# RevolvingStageController.net
KiCad netlist of a schematic drawn in Altium Designer
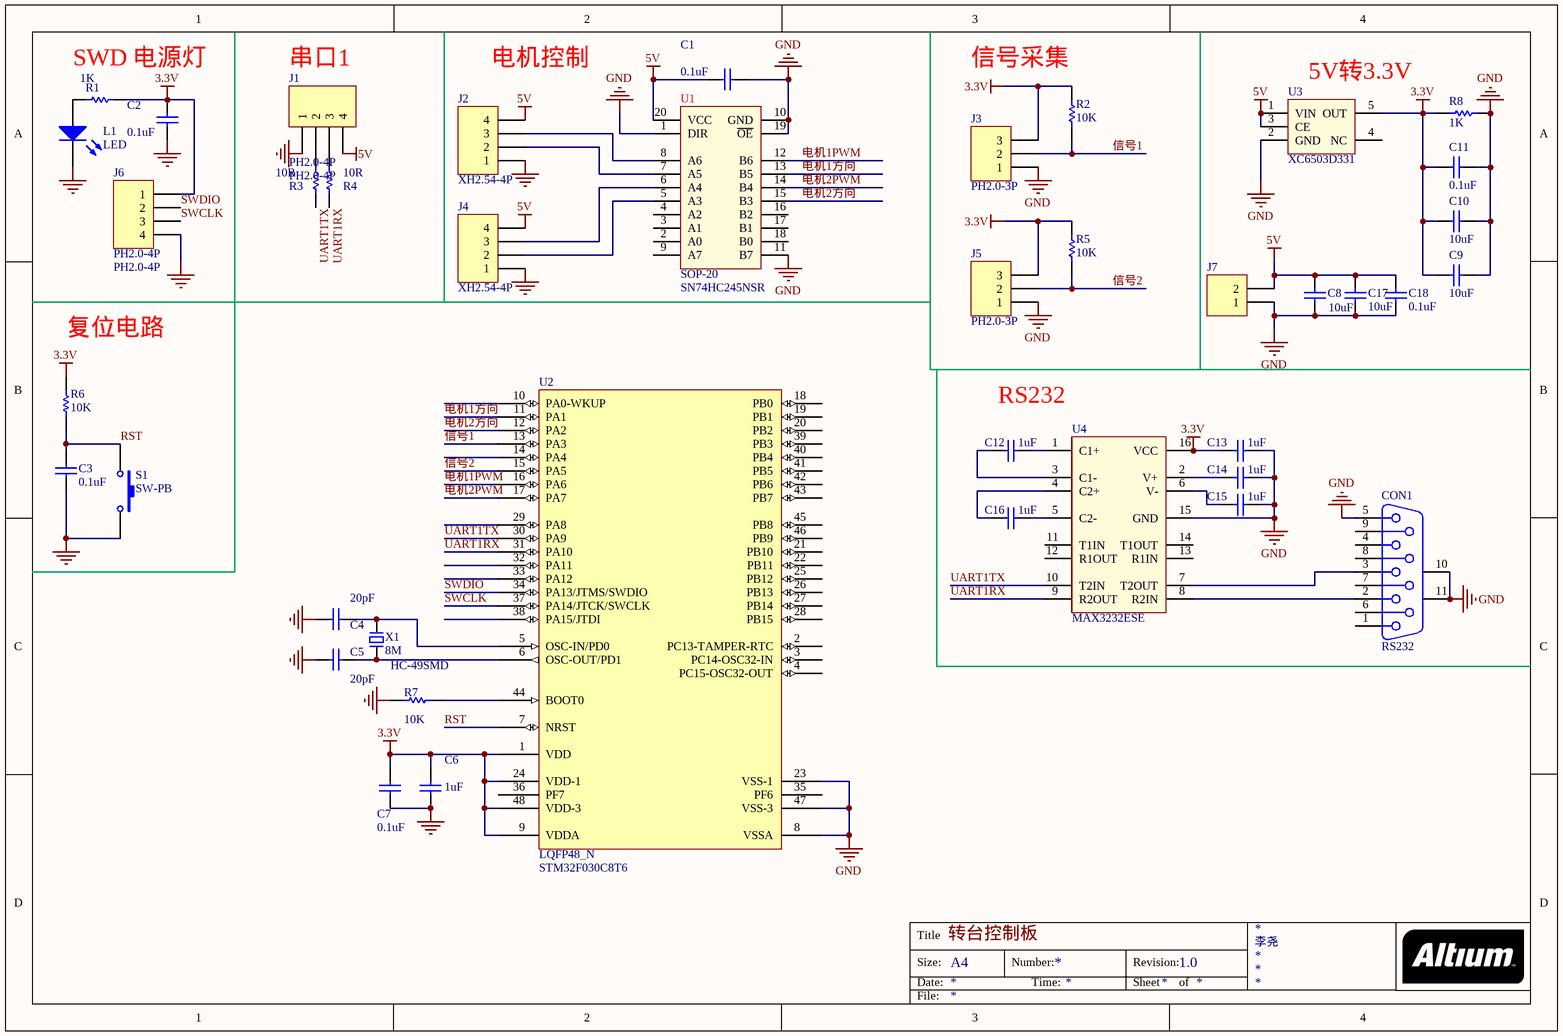
[diagram p0: RevolvingStageController.SchDoc]

(export (version "E")
  (design (tool "Eeschema 10.0.6"))
  (components
    (comp (ref "C1")
      (value "0.1uF")
      (footprint "0603")
      (description "Capacitor")
      (fields (field (name "PUBLISHER") "Altium Limited"))
      (libsource (lib "Miscellaneous Devices") (part "Cap"))
    )
    (comp (ref "C2")
      (value "0.1uF")
      (footprint "0603")
      (description "Capacitor")
      (fields (field (name "PUBLISHER") "Altium Limited"))
      (libsource (lib "Miscellaneous Devices") (part "Cap"))
    )
    (comp (ref "C3")
      (value "0.1uF")
      (footprint "0603")
      (description "Capacitor")
      (fields (field (name "PUBLISHER") "Altium Limited"))
      (libsource (lib "Miscellaneous Devices") (part "Cap"))
    )
    (comp (ref "C4")
      (value "20pF")
      (footprint "0603")
      (description "Capacitor")
      (fields (field (name "PUBLISHER") "Altium Limited"))
      (libsource (lib "Miscellaneous Devices") (part "Cap"))
    )
    (comp (ref "C5")
      (value "20pF")
      (footprint "0603")
      (description "Capacitor")
      (fields (field (name "PUBLISHER") "Altium Limited"))
      (libsource (lib "Miscellaneous Devices") (part "Cap"))
    )
    (comp (ref "C6")
      (value "1uF")
      (footprint "0603")
      (description "Capacitor")
      (fields (field (name "PUBLISHER") "Altium Limited"))
      (libsource (lib "Miscellaneous Devices") (part "Cap"))
    )
    (comp (ref "C7")
      (value "0.1uF")
      (footprint "0603")
      (description "Capacitor")
      (fields (field (name "PUBLISHER") "Altium Limited"))
      (libsource (lib "Miscellaneous Devices") (part "Cap"))
    )
    (comp (ref "C8")
      (value "10uF")
      (footprint "0603")
      (description "Capacitor")
      (fields (field (name "PUBLISHER") "Altium Limited"))
      (libsource (lib "Miscellaneous Devices") (part "Cap"))
    )
    (comp (ref "C9")
      (value "10uF")
      (footprint "0603")
      (description "Capacitor")
      (fields (field (name "PUBLISHER") "Altium Limited"))
      (libsource (lib "Miscellaneous Devices") (part "Cap"))
    )
    (comp (ref "C10")
      (value "10uF")
      (footprint "0603")
      (description "Capacitor")
      (fields (field (name "PUBLISHER") "Altium Limited"))
      (libsource (lib "Miscellaneous Devices") (part "Cap"))
    )
    (comp (ref "C11")
      (value "0.1uF")
      (footprint "0603")
      (description "Capacitor")
      (fields (field (name "PUBLISHER") "Altium Limited"))
      (libsource (lib "Miscellaneous Devices") (part "Cap"))
    )
    (comp (ref "C12")
      (value "1uF")
      (footprint "LiyaoPCB库:0603")
      (description "Capacitor")
      (fields (field (name "PUBLISHER") "Altium Limited"))
      (libsource (lib "Miscellaneous Devices") (part "Cap"))
    )
    (comp (ref "C13")
      (value "1uF")
      (footprint "0603")
      (description "Capacitor")
      (fields (field (name "PUBLISHER") "Altium Limited"))
      (libsource (lib "Miscellaneous Devices") (part "Cap"))
    )
    (comp (ref "C14")
      (value "1uF")
      (footprint "0603")
      (description "Capacitor")
      (fields (field (name "PUBLISHER") "Altium Limited"))
      (libsource (lib "Miscellaneous Devices") (part "Cap"))
    )
    (comp (ref "C15")
      (value "1uF")
      (footprint "0603")
      (description "Capacitor")
      (fields (field (name "PUBLISHER") "Altium Limited"))
      (libsource (lib "Miscellaneous Devices") (part "Cap"))
    )
    (comp (ref "C16")
      (value "1uF")
      (footprint "0603")
      (description "Capacitor")
      (fields (field (name "PUBLISHER") "Altium Limited"))
      (libsource (lib "Miscellaneous Devices") (part "Cap"))
    )
    (comp (ref "C17")
      (value "10uF")
      (footprint "0603")
      (description "电容0603")
      (fields (field (name "PUBLISHER") "Altium Limited"))
      (libsource (lib "Liyao原理图库") (part "Cap"))
    )
    (comp (ref "C18")
      (value "0.1uF")
      (footprint "0603")
      (description "电容0603")
      (fields (field (name "PUBLISHER") "Altium Limited"))
      (libsource (lib "Liyao原理图库") (part "Cap"))
    )
    (comp (ref "CON1")
      (value "RS232")
      (footprint "DSUB1.385-2H9-M")
      (description "Receptacle Assembly, 9 Position, Right Angle")
      (fields (field (name "PUBLISHER") "Altium Limited"))
      (libsource (lib "Liyao原理图库") (part "D Connector 9"))
    )
    (comp (ref "J1")
      (value "PH2.0-4P")
      (footprint "PH2.0-4P")
      (description "Header, 4-Pin")
      (fields (field (name "ALTIUM_VALUE") "PH2.0-4P") (field (name "PUBLISHER") "Altium Limited"))
      (libsource (lib "Miscellaneous Connectors") (part "Header 4"))
    )
    (comp (ref "J2")
      (value "XH2.54-4P")
      (footprint "XH2.54-4")
      (description "Header, 4-Pin")
      (fields (field (name "PUBLISHER") "Altium Limited"))
      (libsource (lib "") (part "Header 4_2"))
    )
    (comp (ref "J3")
      (value "PH2.0-3P")
      (footprint "PH2.0-3P")
      (description "Header, 3-Pin")
      (fields (field (name "PUBLISHER") "Altium Limited"))
      (libsource (lib "Sparks") (part "Header 3"))
    )
    (comp (ref "J4")
      (value "XH2.54-4P")
      (footprint "XH2.54-4")
      (description "Header, 4-Pin")
      (fields (field (name "PUBLISHER") "Altium Limited"))
      (libsource (lib "") (part "Header 4_2"))
    )
    (comp (ref "J5")
      (value "PH2.0-3P")
      (footprint "PH2.0-3P")
      (description "Header, 3-Pin")
      (fields (field (name "PUBLISHER") "Altium Limited"))
      (libsource (lib "Sparks") (part "Header 3"))
    )
    (comp (ref "J6")
      (value "PH2.0-4P")
      (footprint "PH2.0-4P")
      (description "Header, 4-Pin")
      (fields (field (name "ALTIUM_VALUE") "PH2.0-4P") (field (name "PUBLISHER") "Altium Limited"))
      (libsource (lib "") (part "Header 4_1"))
    )
    (comp (ref "J7")
      (value "PH2.0-2P")
      (footprint "PH2.0-2P")
      (description "插座PH2.0-2P")
      (fields (field (name "PUBLISHER") "Altium Limited"))
      (libsource (lib "Liyao原理图库") (part "PH2.0-2P"))
    )
    (comp (ref "L1") (value "LED") (footprint "0603") (libsource (lib "Sparks") (part "LED")))
    (comp (ref "R1")
      (value "1K")
      (footprint "0603")
      (description "Resistor")
      (fields (field (name "PUBLISHER") "Altium Limited"))
      (libsource (lib "Miscellaneous Devices") (part "Res1"))
    )
    (comp (ref "R2")
      (value "10K")
      (footprint "0603")
      (description "Resistor")
      (fields (field (name "PUBLISHER") "Altium Limited"))
      (libsource (lib "Miscellaneous Devices") (part "Res1"))
    )
    (comp (ref "R3")
      (value "10R")
      (footprint "0603")
      (description "Resistor")
      (fields (field (name "PUBLISHER") "Altium Limited"))
      (libsource (lib "Miscellaneous Devices") (part "Res1"))
    )
    (comp (ref "R4")
      (value "10R")
      (footprint "0603")
      (description "Resistor")
      (fields (field (name "PUBLISHER") "Altium Limited"))
      (libsource (lib "Miscellaneous Devices") (part "Res1"))
    )
    (comp (ref "R5")
      (value "10K")
      (footprint "0603")
      (description "Resistor")
      (fields (field (name "PUBLISHER") "Altium Limited"))
      (libsource (lib "Miscellaneous Devices") (part "Res1"))
    )
    (comp (ref "R6")
      (value "10K")
      (footprint "0603")
      (description "Resistor")
      (fields (field (name "PUBLISHER") "Altium Limited"))
      (libsource (lib "Miscellaneous Devices") (part "Res1"))
    )
    (comp (ref "R7")
      (value "10K")
      (footprint "0603")
      (description "Resistor")
      (fields (field (name "PUBLISHER") "Altium Limited"))
      (libsource (lib "Miscellaneous Devices") (part "Res1"))
    )
    (comp (ref "R8")
      (value "1K")
      (footprint "0603")
      (description "Resistor")
      (fields (field (name "PUBLISHER") "Altium Limited"))
      (libsource (lib "Miscellaneous Devices") (part "Res1"))
    )
    (comp (ref "S1")
      (value "SW-PB")
      (footprint "SW-KEY")
      (description "Switch")
      (fields (field (name "PUBLISHER") "Altium Limited"))
      (libsource (lib "Miscellaneous Devices") (part "SW-PB"))
    )
    (comp (ref "U1")
      (value "SOP-20")
      (footprint "SOP-20")
      (fields (field (name "ALTIUM_VALUE") "SN74HC245NSR"))
      (libsource (lib "SCH") (part "74HC245"))
    )
    (comp (ref "U2")
      (value "LQFP48_N")
      (footprint "LQFP48_N")
      (description "STM32 ARM-based 32-bit MCU with 64 Kbytes Flash, 48-pin LQFP, Industrial Temperature")
      (fields (field (name "ALTIUM_VALUE") "STM32F030C8T6") (field (name "PUBLISHER") "*"))
      (libsource (lib "Liyao原理图库") (part "STM32F030C8T6"))
    )
    (comp (ref "U3")
      (value "XC6503D331")
      (footprint "SOT23-5")
      (libsource (lib "CYSchlib") (part "XC6503Dxxx"))
    )
    (comp (ref "U4")
      (value "MAX3232ESE")
      (footprint "SOIC-16N")
      (libsource (lib "Liyao原理图库") (part "MAX3232"))
    )
    (comp (ref "X1")
      (value "8M")
      (footprint "HC-49SMD")
      (fields (field (name "ALTIUM_VALUE") "HC-49SMD"))
      (libsource (lib "CYSchlib") (part "XTAL"))
    )
  )
  (nets
    (net (code "1") (name "/RST") (class "Default")
      (node (ref "C3") (pin "1") (pinfunction "1_1") (pintype "passive"))
      (node (ref "R6") (pin "2") (pinfunction "2_2") (pintype "passive"))
      (node (ref "S1") (pin "1") (pinfunction "1_1") (pintype "passive"))
      (node (ref "U2") (pin "7") (pinfunction "NRST_7") (pintype "bidirectional"))
    )
    (net (code "2") (name "/SWCLK") (class "Default")
      (node (ref "J6") (pin "3") (pinfunction "3_3") (pintype "passive"))
      (node (ref "U2") (pin "37") (pinfunction "PA14/JTCK/SWCLK_37") (pintype "bidirectional"))
    )
    (net (code "3") (name "/SWDIO") (class "Default")
      (node (ref "J6") (pin "2") (pinfunction "2_2") (pintype "passive"))
      (node (ref "U2") (pin "34") (pinfunction "PA13/JTMS/SWDIO_34") (pintype "bidirectional"))
    )
    (net (code "4") (name "/UART1RX") (class "Default")
      (node (ref "R4") (pin "2") (pinfunction "2_2") (pintype "passive"))
      (node (ref "U2") (pin "31") (pinfunction "PA10_31") (pintype "bidirectional"))
      (node (ref "U4") (pin "9") (pinfunction "R2OUT_9") (pintype "passive"))
    )
    (net (code "5") (name "/UART1TX") (class "Default")
      (node (ref "R3") (pin "2") (pinfunction "2_2") (pintype "passive"))
      (node (ref "U2") (pin "30") (pinfunction "PA9_30") (pintype "bidirectional"))
      (node (ref "U4") (pin "10") (pinfunction "T2IN_10") (pintype "passive"))
    )
    (net (code "6") (name "/信号1") (class "Default")
      (node (ref "J3") (pin "2") (pinfunction "2_2") (pintype "passive"))
      (node (ref "R2") (pin "2") (pinfunction "2_2") (pintype "passive"))
      (node (ref "U2") (pin "13") (pinfunction "PA3_13") (pintype "bidirectional"))
    )
    (net (code "7") (name "/信号2") (class "Default")
      (node (ref "J5") (pin "2") (pinfunction "2_2") (pintype "passive"))
      (node (ref "R5") (pin "2") (pinfunction "2_2") (pintype "passive"))
      (node (ref "U2") (pin "15") (pinfunction "PA5_15") (pintype "bidirectional"))
    )
    (net (code "8") (name "/电机1PWM") (class "Default")
      (node (ref "U1") (pin "12") (pinfunction "B6_12") (pintype "passive"))
      (node (ref "U2") (pin "16") (pinfunction "PA6_16") (pintype "bidirectional"))
    )
    (net (code "9") (name "/电机1方向") (class "Default")
      (node (ref "U1") (pin "13") (pinfunction "B5_13") (pintype "passive"))
      (node (ref "U2") (pin "11") (pinfunction "PA1_11") (pintype "bidirectional"))
    )
    (net (code "10") (name "/电机2PWM") (class "Default")
      (node (ref "U1") (pin "14") (pinfunction "B4_14") (pintype "passive"))
      (node (ref "U2") (pin "17") (pinfunction "PA7_17") (pintype "bidirectional"))
    )
    (net (code "11") (name "/电机2方向") (class "Default")
      (node (ref "U1") (pin "15") (pinfunction "B3_15") (pintype "passive"))
      (node (ref "U2") (pin "12") (pinfunction "PA2_12") (pintype "bidirectional"))
    )
    (net (code "12") (name "3.3V") (class "Default")
      (node (ref "C10") (pin "2") (pinfunction "2_2") (pintype "passive"))
      (node (ref "C11") (pin "2") (pinfunction "2_2") (pintype "passive"))
      (node (ref "C13") (pin "2") (pinfunction "2_2") (pintype "passive"))
      (node (ref "C2") (pin "1") (pinfunction "1_1") (pintype "passive"))
      (node (ref "C6") (pin "1") (pinfunction "1_1") (pintype "passive"))
      (node (ref "C7") (pin "1") (pinfunction "1_1") (pintype "passive"))
      (node (ref "C9") (pin "1") (pinfunction "1_1") (pintype "passive"))
      (node (ref "J3") (pin "3") (pinfunction "3_3") (pintype "passive"))
      (node (ref "J5") (pin "3") (pinfunction "3_3") (pintype "passive"))
      (node (ref "J6") (pin "1") (pinfunction "1_1") (pintype "passive"))
      (node (ref "R1") (pin "2") (pinfunction "2_2") (pintype "passive"))
      (node (ref "R2") (pin "1") (pinfunction "1_1") (pintype "passive"))
      (node (ref "R5") (pin "1") (pinfunction "1_1") (pintype "passive"))
      (node (ref "R6") (pin "1") (pinfunction "1_1") (pintype "passive"))
      (node (ref "R8") (pin "2") (pinfunction "2_2") (pintype "passive"))
      (node (ref "U2") (pin "1") (pinfunction "VDD_1") (pintype "power_in"))
      (node (ref "U2") (pin "24") (pinfunction "VDD-1_24") (pintype "power_in"))
      (node (ref "U2") (pin "48") (pinfunction "VDD-3_48") (pintype "power_in"))
      (node (ref "U2") (pin "9") (pinfunction "VDDA_9") (pintype "power_in"))
      (node (ref "U3") (pin "5") (pinfunction "OUT_5") (pintype "passive"))
      (node (ref "U4") (pin "16") (pinfunction "VCC_16") (pintype "passive"))
    )
    (net (code "13") (name "5V") (class "Default")
      (node (ref "C1") (pin "1") (pinfunction "1_1") (pintype "passive"))
      (node (ref "C17") (pin "2") (pinfunction "2_2") (pintype "passive"))
      (node (ref "C18") (pin "2") (pinfunction "2_2") (pintype "passive"))
      (node (ref "C8") (pin "2") (pinfunction "2_2") (pintype "passive"))
      (node (ref "J1") (pin "4") (pinfunction "4_4") (pintype "passive"))
      (node (ref "J2") (pin "4") (pinfunction "4_4") (pintype "passive"))
      (node (ref "J4") (pin "4") (pinfunction "4_4") (pintype "passive"))
      (node (ref "J7") (pin "2") (pinfunction "2_2") (pintype "passive"))
      (node (ref "U1") (pin "20") (pinfunction "VCC_20") (pintype "passive"))
      (node (ref "U3") (pin "1") (pinfunction "VIN_1") (pintype "passive"))
      (node (ref "U3") (pin "3") (pinfunction "CE_3") (pintype "passive"))
    )
    (net (code "14") (name "GND") (class "Default")
      (node (ref "C1") (pin "2") (pinfunction "2_2") (pintype "passive"))
      (node (ref "C10") (pin "1") (pinfunction "1_1") (pintype "passive"))
      (node (ref "C11") (pin "1") (pinfunction "1_1") (pintype "passive"))
      (node (ref "C13") (pin "1") (pinfunction "1_1") (pintype "passive"))
      (node (ref "C14") (pin "1") (pinfunction "1_1") (pintype "passive"))
      (node (ref "C15") (pin "1") (pinfunction "1_1") (pintype "passive"))
      (node (ref "C17") (pin "1") (pinfunction "1_1") (pintype "passive"))
      (node (ref "C18") (pin "1") (pinfunction "1_1") (pintype "passive"))
      (node (ref "C2") (pin "2") (pinfunction "2_2") (pintype "passive"))
      (node (ref "C3") (pin "2") (pinfunction "2_2") (pintype "passive"))
      (node (ref "C4") (pin "1") (pinfunction "1_1") (pintype "passive"))
      (node (ref "C5") (pin "1") (pinfunction "1_1") (pintype "passive"))
      (node (ref "C6") (pin "2") (pinfunction "2_2") (pintype "passive"))
      (node (ref "C7") (pin "2") (pinfunction "2_2") (pintype "passive"))
      (node (ref "C8") (pin "1") (pinfunction "1_1") (pintype "passive"))
      (node (ref "C9") (pin "2") (pinfunction "2_2") (pintype "passive"))
      (node (ref "CON1") (pin "10") (pinfunction "MH1_10") (pintype "passive"))
      (node (ref "CON1") (pin "11") (pinfunction "MH2_11") (pintype "passive"))
      (node (ref "CON1") (pin "5") (pinfunction "5_5") (pintype "passive"))
      (node (ref "J1") (pin "1") (pinfunction "1_1") (pintype "passive"))
      (node (ref "J2") (pin "1") (pinfunction "1_1") (pintype "passive"))
      (node (ref "J3") (pin "1") (pinfunction "1_1") (pintype "passive"))
      (node (ref "J4") (pin "1") (pinfunction "1_1") (pintype "passive"))
      (node (ref "J5") (pin "1") (pinfunction "1_1") (pintype "passive"))
      (node (ref "J6") (pin "4") (pinfunction "4_4") (pintype "passive"))
      (node (ref "J7") (pin "1") (pinfunction "1_1") (pintype "passive"))
      (node (ref "L1") (pin "2") (pinfunction "K_2") (pintype "passive"))
      (node (ref "R7") (pin "1") (pinfunction "1_1") (pintype "passive"))
      (node (ref "R8") (pin "1") (pinfunction "1_1") (pintype "passive"))
      (node (ref "S1") (pin "2") (pinfunction "2_2") (pintype "passive"))
      (node (ref "U1") (pin "1") (pinfunction "DIR_1") (pintype "passive"))
      (node (ref "U1") (pin "10") (pinfunction "GND_10") (pintype "passive"))
      (node (ref "U1") (pin "11") (pinfunction "B7_11") (pintype "passive"))
      (node (ref "U1") (pin "19") (pinfunction "~{OE}_19") (pintype "passive"))
      (node (ref "U2") (pin "23") (pinfunction "VSS-1_23") (pintype "power_in"))
      (node (ref "U2") (pin "47") (pinfunction "VSS-3_47") (pintype "power_in"))
      (node (ref "U2") (pin "8") (pinfunction "VSSA_8") (pintype "power_in"))
      (node (ref "U3") (pin "2") (pinfunction "GND_2") (pintype "passive"))
      (node (ref "U4") (pin "15") (pinfunction "GND_15") (pintype "passive"))
    )
    (net (code "15") (name "Net-(J1-Pad2)") (class "Default")
      (node (ref "J1") (pin "2") (pinfunction "2_2") (pintype "passive"))
      (node (ref "R3") (pin "1") (pinfunction "1_1") (pintype "passive"))
    )
    (net (code "16") (name "Net-(J1-Pad3)") (class "Default")
      (node (ref "J1") (pin "3") (pinfunction "3_3") (pintype "passive"))
      (node (ref "R4") (pin "1") (pinfunction "1_1") (pintype "passive"))
    )
    (net (code "17") (name "Net-(L1-A)") (class "Default")
      (node (ref "L1") (pin "1") (pinfunction "A_1") (pintype "passive"))
      (node (ref "R1") (pin "1") (pinfunction "1_1") (pintype "passive"))
    )
    (net (code "18") (name "Net-(U1-A3)") (class "Default")
      (node (ref "J4") (pin "2") (pinfunction "2_2") (pintype "passive"))
      (node (ref "U1") (pin "5") (pinfunction "A3_5") (pintype "passive"))
    )
    (net (code "19") (name "Net-(U1-A4)") (class "Default")
      (node (ref "J4") (pin "3") (pinfunction "3_3") (pintype "passive"))
      (node (ref "U1") (pin "6") (pinfunction "A4_6") (pintype "passive"))
    )
    (net (code "20") (name "Net-(U1-A5)") (class "Default")
      (node (ref "J2") (pin "2") (pinfunction "2_2") (pintype "passive"))
      (node (ref "U1") (pin "7") (pinfunction "A5_7") (pintype "passive"))
    )
    (net (code "21") (name "Net-(U1-A6)") (class "Default")
      (node (ref "J2") (pin "3") (pinfunction "3_3") (pintype "passive"))
      (node (ref "U1") (pin "8") (pinfunction "A6_8") (pintype "passive"))
    )
    (net (code "22") (name "Net-(U2-BOOT0)") (class "Default")
      (node (ref "R7") (pin "2") (pinfunction "2_2") (pintype "passive"))
      (node (ref "U2") (pin "44") (pinfunction "BOOT0_44") (pintype "input"))
    )
    (net (code "23") (name "Net-(U2-OSC-IN{slash}PD0)") (class "Default")
      (node (ref "C4") (pin "2") (pinfunction "2_2") (pintype "passive"))
      (node (ref "U2") (pin "5") (pinfunction "OSC-IN/PD0_5") (pintype "input"))
      (node (ref "X1") (pin "2") (pinfunction "2_2") (pintype "passive"))
    )
    (net (code "24") (name "Net-(U2-OSC-OUT{slash}PD1)") (class "Default")
      (node (ref "C5") (pin "2") (pinfunction "2_2") (pintype "passive"))
      (node (ref "U2") (pin "6") (pinfunction "OSC-OUT/PD1_6") (pintype "output"))
      (node (ref "X1") (pin "1") (pinfunction "1_1") (pintype "passive"))
    )
    (net (code "25") (name "Net-(U4-C1+)") (class "Default")
      (node (ref "C12") (pin "1") (pinfunction "1_1") (pintype "passive"))
      (node (ref "U4") (pin "1") (pinfunction "C1+_1") (pintype "passive"))
    )
    (net (code "26") (name "Net-(U4-C1-)") (class "Default")
      (node (ref "C12") (pin "2") (pinfunction "2_2") (pintype "passive"))
      (node (ref "U4") (pin "3") (pinfunction "C1-_3") (pintype "passive"))
    )
    (net (code "27") (name "Net-(U4-C2+)") (class "Default")
      (node (ref "C16") (pin "2") (pinfunction "2_2") (pintype "passive"))
      (node (ref "U4") (pin "4") (pinfunction "C2+_4") (pintype "passive"))
    )
    (net (code "28") (name "Net-(U4-C2-)") (class "Default")
      (node (ref "C16") (pin "1") (pinfunction "1_1") (pintype "passive"))
      (node (ref "U4") (pin "5") (pinfunction "C2-_5") (pintype "passive"))
    )
    (net (code "29") (name "Net-(U4-R2IN)") (class "Default")
      (node (ref "CON1") (pin "2") (pinfunction "2_2") (pintype "passive"))
      (node (ref "U4") (pin "8") (pinfunction "R2IN_8") (pintype "passive"))
    )
    (net (code "30") (name "Net-(U4-T2OUT)") (class "Default")
      (node (ref "CON1") (pin "3") (pinfunction "3_3") (pintype "passive"))
      (node (ref "U4") (pin "7") (pinfunction "T2OUT_7") (pintype "passive"))
    )
    (net (code "31") (name "Net-(U4-V+)") (class "Default")
      (node (ref "C14") (pin "2") (pinfunction "2_2") (pintype "passive"))
      (node (ref "U4") (pin "2") (pinfunction "V+_2") (pintype "passive"))
    )
    (net (code "32") (name "Net-(U4-V-)") (class "Default")
      (node (ref "C15") (pin "2") (pinfunction "2_2") (pintype "passive"))
      (node (ref "U4") (pin "6") (pinfunction "V-_6") (pintype "passive"))
    )
    (net (code "33") (name "unconnected-(CON1-Pad1)") (class "Default")
      (node (ref "CON1") (pin "1") (pinfunction "1_1") (pintype "passive"))
    )
    (net (code "34") (name "unconnected-(CON1-Pad4)") (class "Default")
      (node (ref "CON1") (pin "4") (pinfunction "4_4") (pintype "passive"))
    )
    (net (code "35") (name "unconnected-(CON1-Pad6)") (class "Default")
      (node (ref "CON1") (pin "6") (pinfunction "6_6") (pintype "passive"))
    )
    (net (code "36") (name "unconnected-(CON1-Pad7)") (class "Default")
      (node (ref "CON1") (pin "7") (pinfunction "7_7") (pintype "passive"))
    )
    (net (code "37") (name "unconnected-(CON1-Pad8)") (class "Default")
      (node (ref "CON1") (pin "8") (pinfunction "8_8") (pintype "passive"))
    )
    (net (code "38") (name "unconnected-(CON1-Pad9)") (class "Default")
      (node (ref "CON1") (pin "9") (pinfunction "9_9") (pintype "passive"))
    )
    (net (code "39") (name "unconnected-(U1-A0-Pad2)") (class "Default")
      (node (ref "U1") (pin "2") (pinfunction "A0_2") (pintype "passive"))
    )
    (net (code "40") (name "unconnected-(U1-A1-Pad3)") (class "Default")
      (node (ref "U1") (pin "3") (pinfunction "A1_3") (pintype "passive"))
    )
    (net (code "41") (name "unconnected-(U1-A2-Pad4)") (class "Default")
      (node (ref "U1") (pin "4") (pinfunction "A2_4") (pintype "passive"))
    )
    (net (code "42") (name "unconnected-(U1-A7-Pad9)") (class "Default")
      (node (ref "U1") (pin "9") (pinfunction "A7_9") (pintype "passive"))
    )
    (net (code "43") (name "unconnected-(U1-B0-Pad18)") (class "Default")
      (node (ref "U1") (pin "18") (pinfunction "B0_18") (pintype "passive"))
    )
    (net (code "44") (name "unconnected-(U1-B1-Pad17)") (class "Default")
      (node (ref "U1") (pin "17") (pinfunction "B1_17") (pintype "passive"))
    )
    (net (code "45") (name "unconnected-(U1-B2-Pad16)") (class "Default")
      (node (ref "U1") (pin "16") (pinfunction "B2_16") (pintype "passive"))
    )
    (net (code "46") (name "unconnected-(U2-PA0-WKUP-Pad10)") (class "Default")
      (node (ref "U2") (pin "10") (pinfunction "PA0-WKUP_10") (pintype "bidirectional"))
    )
    (net (code "47") (name "unconnected-(U2-PA4-Pad14)") (class "Default")
      (node (ref "U2") (pin "14") (pinfunction "PA4_14") (pintype "bidirectional"))
    )
    (net (code "48") (name "unconnected-(U2-PA8-Pad29)") (class "Default")
      (node (ref "U2") (pin "29") (pinfunction "PA8_29") (pintype "bidirectional"))
    )
    (net (code "49") (name "unconnected-(U2-PA11-Pad32)") (class "Default")
      (node (ref "U2") (pin "32") (pinfunction "PA11_32") (pintype "bidirectional"))
    )
    (net (code "50") (name "unconnected-(U2-PA12-Pad33)") (class "Default")
      (node (ref "U2") (pin "33") (pinfunction "PA12_33") (pintype "bidirectional"))
    )
    (net (code "51") (name "unconnected-(U2-PA15{slash}JTDI-Pad38)") (class "Default")
      (node (ref "U2") (pin "38") (pinfunction "PA15/JTDI_38") (pintype "bidirectional"))
    )
    (net (code "52") (name "unconnected-(U2-PB0-Pad18)") (class "Default")
      (node (ref "U2") (pin "18") (pinfunction "PB0_18") (pintype "bidirectional"))
    )
    (net (code "53") (name "unconnected-(U2-PB1-Pad19)") (class "Default")
      (node (ref "U2") (pin "19") (pinfunction "PB1_19") (pintype "bidirectional"))
    )
    (net (code "54") (name "unconnected-(U2-PB2-Pad20)") (class "Default")
      (node (ref "U2") (pin "20") (pinfunction "PB2_20") (pintype "bidirectional"))
    )
    (net (code "55") (name "unconnected-(U2-PB3-Pad39)") (class "Default")
      (node (ref "U2") (pin "39") (pinfunction "PB3_39") (pintype "bidirectional"))
    )
    (net (code "56") (name "unconnected-(U2-PB4-Pad40)") (class "Default")
      (node (ref "U2") (pin "40") (pinfunction "PB4_40") (pintype "bidirectional"))
    )
    (net (code "57") (name "unconnected-(U2-PB5-Pad41)") (class "Default")
      (node (ref "U2") (pin "41") (pinfunction "PB5_41") (pintype "bidirectional"))
    )
    (net (code "58") (name "unconnected-(U2-PB6-Pad42)") (class "Default")
      (node (ref "U2") (pin "42") (pinfunction "PB6_42") (pintype "bidirectional"))
    )
    (net (code "59") (name "unconnected-(U2-PB7-Pad43)") (class "Default")
      (node (ref "U2") (pin "43") (pinfunction "PB7_43") (pintype "bidirectional"))
    )
    (net (code "60") (name "unconnected-(U2-PB8-Pad45)") (class "Default")
      (node (ref "U2") (pin "45") (pinfunction "PB8_45") (pintype "bidirectional"))
    )
    (net (code "61") (name "unconnected-(U2-PB9-Pad46)") (class "Default")
      (node (ref "U2") (pin "46") (pinfunction "PB9_46") (pintype "bidirectional"))
    )
    (net (code "62") (name "unconnected-(U2-PB10-Pad21)") (class "Default")
      (node (ref "U2") (pin "21") (pinfunction "PB10_21") (pintype "bidirectional"))
    )
    (net (code "63") (name "unconnected-(U2-PB11-Pad22)") (class "Default")
      (node (ref "U2") (pin "22") (pinfunction "PB11_22") (pintype "bidirectional"))
    )
    (net (code "64") (name "unconnected-(U2-PB12-Pad25)") (class "Default")
      (node (ref "U2") (pin "25") (pinfunction "PB12_25") (pintype "bidirectional"))
    )
    (net (code "65") (name "unconnected-(U2-PB13-Pad26)") (class "Default")
      (node (ref "U2") (pin "26") (pinfunction "PB13_26") (pintype "bidirectional"))
    )
    (net (code "66") (name "unconnected-(U2-PB14-Pad27)") (class "Default")
      (node (ref "U2") (pin "27") (pinfunction "PB14_27") (pintype "bidirectional"))
    )
    (net (code "67") (name "unconnected-(U2-PB15-Pad28)") (class "Default")
      (node (ref "U2") (pin "28") (pinfunction "PB15_28") (pintype "bidirectional"))
    )
    (net (code "68") (name "unconnected-(U2-PC13-TAMPER-RTC-Pad2)") (class "Default")
      (node (ref "U2") (pin "2") (pinfunction "PC13-TAMPER-RTC_2") (pintype "bidirectional"))
    )
    (net (code "69") (name "unconnected-(U2-PC14-OSC32-IN-Pad3)") (class "Default")
      (node (ref "U2") (pin "3") (pinfunction "PC14-OSC32-IN_3") (pintype "bidirectional"))
    )
    (net (code "70") (name "unconnected-(U2-PC15-OSC32-OUT-Pad4)") (class "Default")
      (node (ref "U2") (pin "4") (pinfunction "PC15-OSC32-OUT_4") (pintype "bidirectional"))
    )
    (net (code "71") (name "unconnected-(U2-PF6-Pad35)") (class "Default")
      (node (ref "U2") (pin "35") (pinfunction "PF6_35") (pintype "power_in"))
    )
    (net (code "72") (name "unconnected-(U2-PF7-Pad36)") (class "Default")
      (node (ref "U2") (pin "36") (pinfunction "PF7_36") (pintype "power_in"))
    )
    (net (code "73") (name "unconnected-(U3-NC-Pad4)") (class "Default")
      (node (ref "U3") (pin "4") (pinfunction "NC_4") (pintype "passive"))
    )
    (net (code "74") (name "unconnected-(U4-R1IN-Pad13)") (class "Default")
      (node (ref "U4") (pin "13") (pinfunction "R1IN_13") (pintype "passive"))
    )
    (net (code "75") (name "unconnected-(U4-R1OUT-Pad12)") (class "Default")
      (node (ref "U4") (pin "12") (pinfunction "R1OUT_12") (pintype "passive"))
    )
    (net (code "76") (name "unconnected-(U4-T1IN-Pad11)") (class "Default")
      (node (ref "U4") (pin "11") (pinfunction "T1IN_11") (pintype "passive"))
    )
    (net (code "77") (name "unconnected-(U4-T1OUT-Pad14)") (class "Default")
      (node (ref "U4") (pin "14") (pinfunction "T1OUT_14") (pintype "passive"))
    )
  )
)
